# RPism_adapterboard_0V3.net
KiCad netlist of a schematic drawn in EAGLE
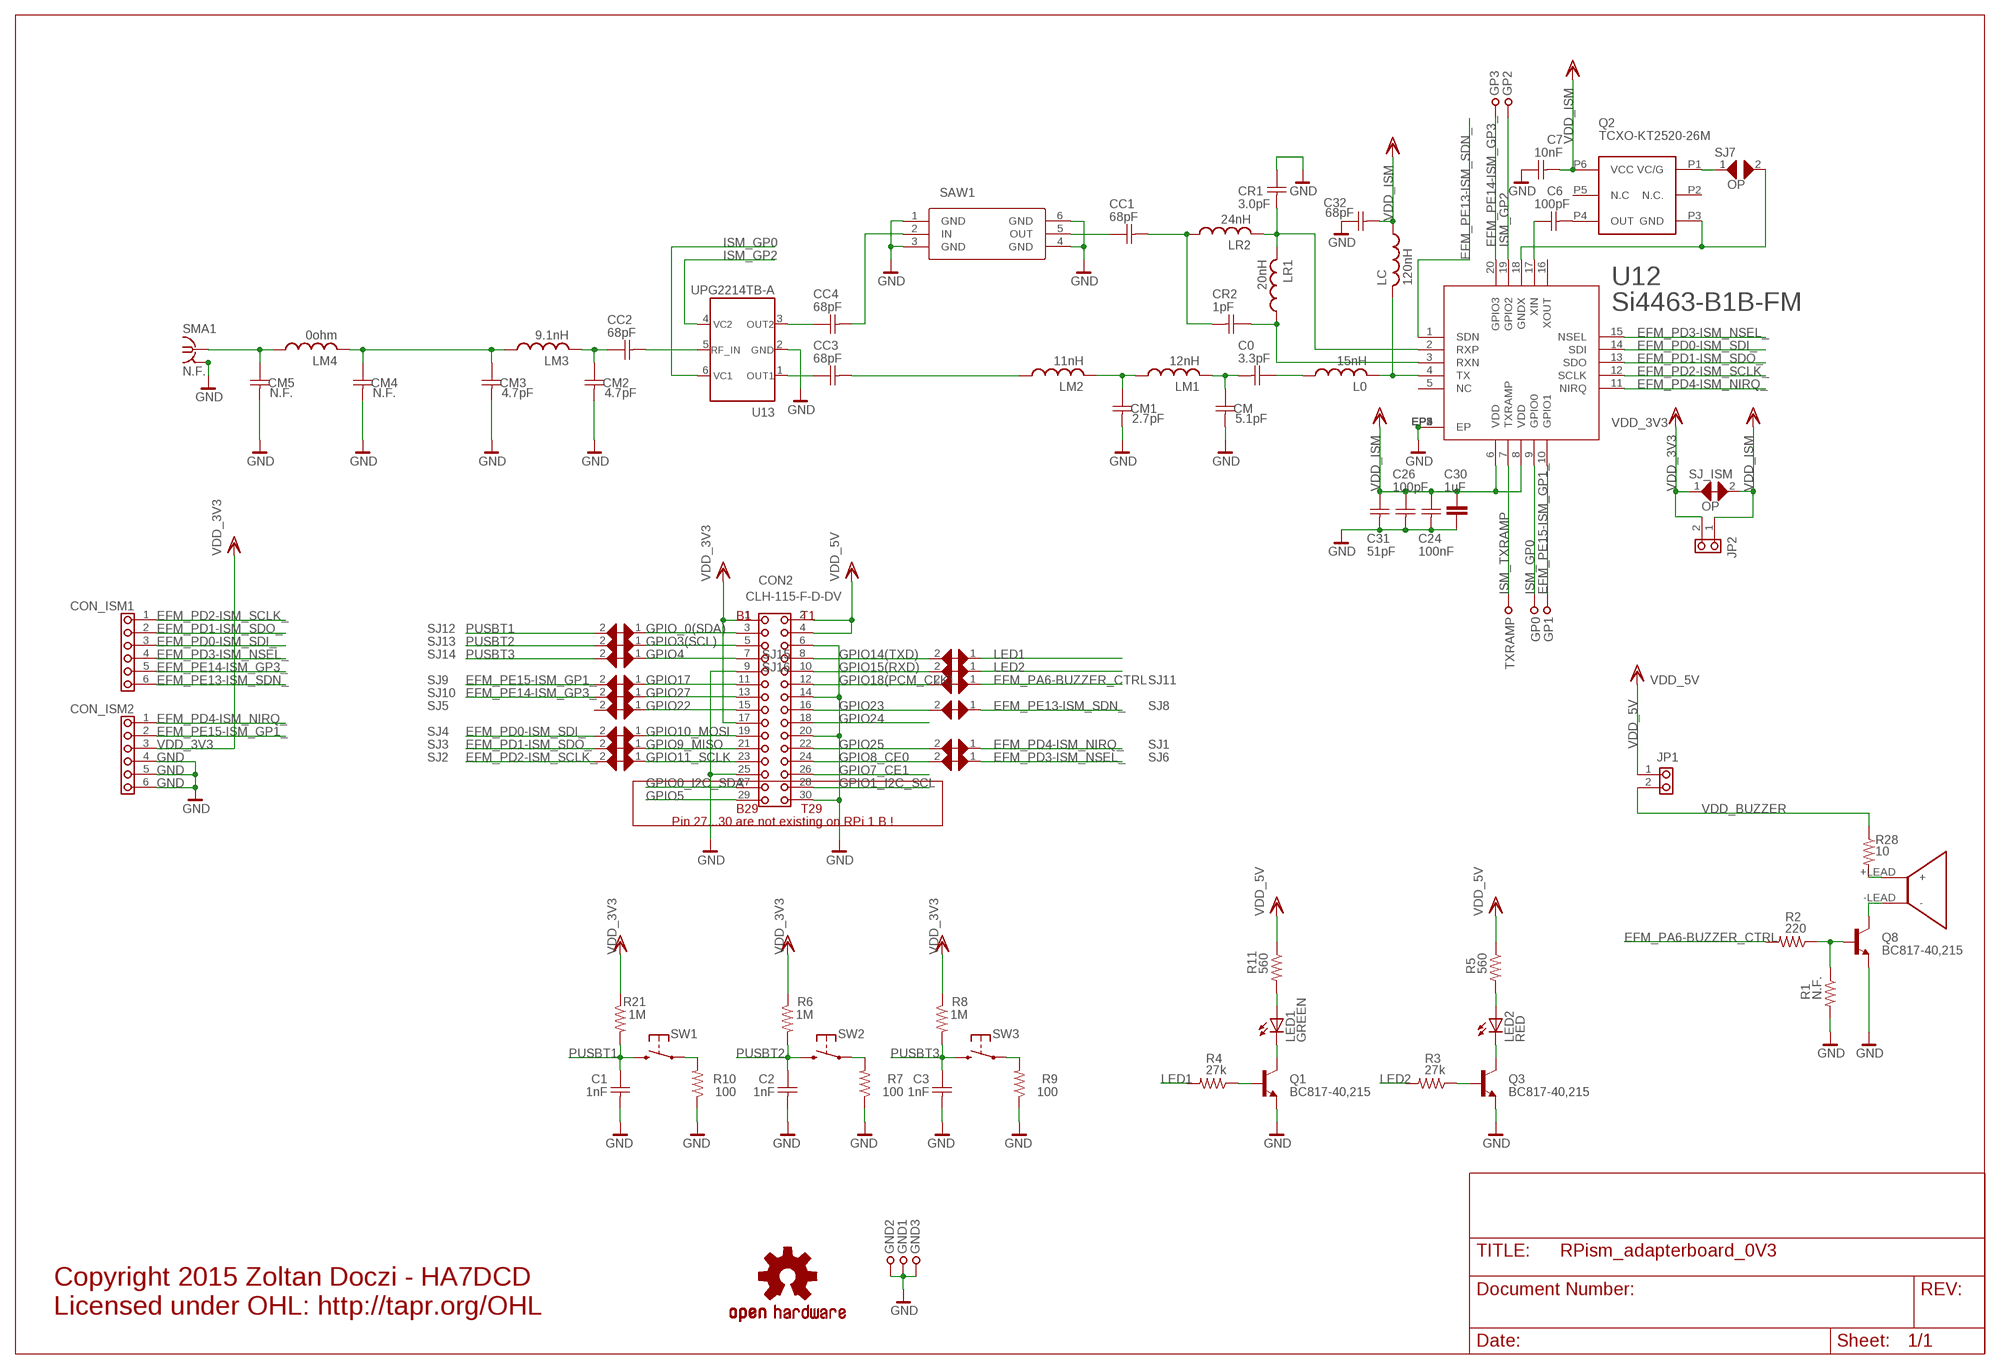
[diagram p0: schematic, sheet 1]

(export (version "E")
  (design (tool "Eeschema 10.0.6"))
  (components
    (comp (ref "BUZZ1")
      (value "SMT-0540-S-R")
      (footprint "eagle-import:SMT-0540-S-R")
      (libsource (lib "eagle-import") (part "SMT-0540-S-R"))
    )
    (comp (ref "C0")
      (value "3.3pF")
      (footprint "eagle-import:CAPC1005X60N")
      (libsource (lib "eagle-import") (part "CAP_GRM15"))
    )
    (comp (ref "C1")
      (value "1nF")
      (footprint "eagle-import:CAPC1005X60N")
      (libsource (lib "eagle-import") (part "CAP_GRM15"))
    )
    (comp (ref "C2")
      (value "1nF")
      (footprint "eagle-import:CAPC1005X60N")
      (libsource (lib "eagle-import") (part "CAP_GRM15"))
    )
    (comp (ref "C3")
      (value "1nF")
      (footprint "eagle-import:CAPC1005X60N")
      (libsource (lib "eagle-import") (part "CAP_GRM15"))
    )
    (comp (ref "C6")
      (value "100pF")
      (footprint "eagle-import:CAPC1005X60N")
      (libsource (lib "eagle-import") (part "CAP_GRM15"))
    )
    (comp (ref "C7")
      (value "10nF")
      (footprint "eagle-import:CAPC1005X60N")
      (libsource (lib "eagle-import") (part "CAP_GRM15"))
    )
    (comp (ref "C24")
      (value "100nF")
      (footprint "eagle-import:CAPC1005X60N")
      (libsource (lib "eagle-import") (part "CAP_GRM15"))
    )
    (comp (ref "C26")
      (value "100pF")
      (footprint "eagle-import:CAPC1005X60N")
      (libsource (lib "eagle-import") (part "CAP_GRM15"))
    )
    (comp (ref "C30")
      (value "1uF")
      (footprint "eagle-import:0603")
      (libsource (lib "eagle-import") (part "CAP-SMD0603"))
    )
    (comp (ref "C31")
      (value "51pF")
      (footprint "eagle-import:CAPC1005X60N")
      (libsource (lib "eagle-import") (part "CAP_GRM15"))
    )
    (comp (ref "C32")
      (value "68pF")
      (footprint "eagle-import:CAPC1005X60N")
      (libsource (lib "eagle-import") (part "CAP_GRM15"))
    )
    (comp (ref "CC1")
      (value "68pF")
      (footprint "eagle-import:CAPC1005X60N")
      (libsource (lib "eagle-import") (part "CAP_GRM15"))
    )
    (comp (ref "CC2")
      (value "68pF")
      (footprint "eagle-import:CAPC1005X60N")
      (libsource (lib "eagle-import") (part "CAP_GRM15"))
    )
    (comp (ref "CC3")
      (value "68pF")
      (footprint "eagle-import:CAPC1005X60N")
      (libsource (lib "eagle-import") (part "CAP_GRM15"))
    )
    (comp (ref "CC4")
      (value "68pF")
      (footprint "eagle-import:CAPC1005X60N")
      (libsource (lib "eagle-import") (part "CAP_GRM15"))
    )
    (comp (ref "CM")
      (value "5.1pF")
      (footprint "eagle-import:CAPC1005X60N")
      (libsource (lib "eagle-import") (part "CAP_GRM15"))
    )
    (comp (ref "CM1")
      (value "2.7pF")
      (footprint "eagle-import:CAPC1005X60N")
      (libsource (lib "eagle-import") (part "CAP_GRM15"))
    )
    (comp (ref "CM2")
      (value "4.7pF")
      (footprint "eagle-import:CAPC1005X60N")
      (libsource (lib "eagle-import") (part "CAP_GRM15"))
    )
    (comp (ref "CM3")
      (value "4.7pF")
      (footprint "eagle-import:CAPC1005X60N")
      (libsource (lib "eagle-import") (part "CAP_GRM15"))
    )
    (comp (ref "CM4")
      (value "N.F.")
      (footprint "eagle-import:CAPC1005X60N")
      (libsource (lib "eagle-import") (part "CAP_GRM15"))
    )
    (comp (ref "CM5")
      (value "N.F.")
      (footprint "eagle-import:CAPC1005X60N")
      (libsource (lib "eagle-import") (part "CAP_GRM15"))
    )
    (comp (ref "CON2")
      (value "CLH-115-F-D-DV")
      (footprint "eagle-import:2X15_SMT_CROSSPCB_ASSYM")
      (libsource (lib "eagle-import") (part "PINHD-2X15_SMD2X15"))
    )
    (comp (ref "CON_ISM1")
      (value "MALE__PIN6S-2MM")
      (footprint "eagle-import:PIN6S_2MM")
      (libsource (lib "eagle-import") (part "PIN6S-2MM"))
    )
    (comp (ref "CON_ISM2")
      (value "FEMALE__PIN6S-2MM")
      (footprint "eagle-import:PIN6S_2MM")
      (libsource (lib "eagle-import") (part "PIN6S-2MM"))
    )
    (comp (ref "CR1")
      (value "3.0pF")
      (footprint "eagle-import:CAPC1005X60N")
      (libsource (lib "eagle-import") (part "CAP_GRM15"))
    )
    (comp (ref "CR2")
      (value "1pF")
      (footprint "eagle-import:CAPC1005X60N")
      (libsource (lib "eagle-import") (part "CAP_GRM15"))
    )
    (comp (ref "GND1")
      (value "TESTPOINT39MIL")
      (footprint "eagle-import:TESTPOINT1,0")
      (libsource (lib "eagle-import") (part "lve_modositott_TESTPOINT39MIL"))
    )
    (comp (ref "GND2")
      (value "TESTPOINT39MIL")
      (footprint "eagle-import:TESTPOINT1,0")
      (libsource (lib "eagle-import") (part "lve_modositott_TESTPOINT39MIL"))
    )
    (comp (ref "GND3")
      (value "TESTPOINT39MIL")
      (footprint "eagle-import:TESTPOINT1,0")
      (libsource (lib "eagle-import") (part "lve_modositott_TESTPOINT39MIL"))
    )
    (comp (ref "GP0")
      (value "TESTPOINT20MIL")
      (footprint "eagle-import:TESTPOINT0,5")
      (libsource (lib "eagle-import") (part "TESTPOINT20MIL"))
    )
    (comp (ref "GP1")
      (value "TESTPOINT20MIL")
      (footprint "eagle-import:TESTPOINT0,5")
      (libsource (lib "eagle-import") (part "TESTPOINT20MIL"))
    )
    (comp (ref "GP2")
      (value "TESTPOINT20MIL")
      (footprint "eagle-import:TESTPOINT0,5")
      (libsource (lib "eagle-import") (part "TESTPOINT20MIL"))
    )
    (comp (ref "GP3")
      (value "TESTPOINT20MIL")
      (footprint "eagle-import:TESTPOINT0,5")
      (libsource (lib "eagle-import") (part "TESTPOINT20MIL"))
    )
    (comp (ref "JP1")
      (value "JUMPER2")
      (footprint "eagle-import:PIN2-1R")
      (libsource (lib "eagle-import") (part "JUMPER2"))
    )
    (comp (ref "JP2")
      (value "N.F.")
      (footprint "eagle-import:PIN2-1R")
      (libsource (lib "eagle-import") (part "JUMPER2"))
    )
    (comp (ref "L0")
      (value "15nH")
      (footprint "eagle-import:0402-INDUCT")
      (fields (field (name "PARTNR") "LQW15AN15NJ00") (field (name "VENDOR") "Murata"))
      (libsource (lib "eagle-import") (part "INDUCT_SMD"))
    )
    (comp (ref "LC")
      (value "120nH")
      (footprint "eagle-import:0402-INDUCT")
      (fields (field (name "PARTNR") "LQW15ANR12J00") (field (name "VENDOR") "Murata"))
      (libsource (lib "eagle-import") (part "INDUCT_SMD"))
    )
    (comp (ref "LED1")
      (value "GREEN")
      (footprint "eagle-import:LED-0603")
      (libsource (lib "eagle-import") (part "LED0603"))
    )
    (comp (ref "LED2")
      (value "RED")
      (footprint "eagle-import:LED-0603")
      (libsource (lib "eagle-import") (part "LED0603"))
    )
    (comp (ref "LM1")
      (value "12nH")
      (footprint "eagle-import:0402-INDUCT")
      (fields (field (name "PARTNR") "LQW15AN12NJ00") (field (name "VENDOR") "Murata"))
      (libsource (lib "eagle-import") (part "INDUCT_SMD"))
    )
    (comp (ref "LM2")
      (value "11nH")
      (footprint "eagle-import:0402-INDUCT")
      (fields (field (name "PARTNR") "LQW15AN11NJ00") (field (name "VENDOR") "Murata"))
      (libsource (lib "eagle-import") (part "INDUCT_SMD"))
    )
    (comp (ref "LM3")
      (value "9.1nH")
      (footprint "eagle-import:0402-INDUCT")
      (fields (field (name "PARTNR") "LQW15AN9N1J00") (field (name "VENDOR") "Murata"))
      (libsource (lib "eagle-import") (part "INDUCT_SMD"))
    )
    (comp (ref "LM4")
      (value "0ohm")
      (footprint "eagle-import:0402-INDUCT")
      (fields (field (name "PARTNR") "LQW15AN12NJ00") (field (name "VENDOR") "Murata"))
      (libsource (lib "eagle-import") (part "INDUCT_SMD"))
    )
    (comp (ref "LR1")
      (value "20nH")
      (footprint "eagle-import:0402-INDUCT")
      (fields (field (name "PARTNR") "LQW15AN20NJ00D") (field (name "VENDOR") "Murata"))
      (libsource (lib "eagle-import") (part "INDUCT_SMD"))
    )
    (comp (ref "LR2")
      (value "24nH")
      (footprint "eagle-import:0402-INDUCT")
      (fields (field (name "PARTNR") "LQW15AN24NJ00D") (field (name "VENDOR") "Murata"))
      (libsource (lib "eagle-import") (part "INDUCT_SMD"))
    )
    (comp (ref "Q1")
      (value "BC817-40,215")
      (footprint "eagle-import:SOT23-BEC")
      (libsource (lib "eagle-import") (part "BC817SMD-16LT1"))
    )
    (comp (ref "Q2")
      (value "TCXO-KT2520-26M")
      (footprint "eagle-import:TCXO_2.5X2MM")
      (libsource (lib "eagle-import") (part "TCXO-KT2520-26M"))
    )
    (comp (ref "Q3")
      (value "BC817-40,215")
      (footprint "eagle-import:SOT23-BEC")
      (libsource (lib "eagle-import") (part "BC817SMD-16LT1"))
    )
    (comp (ref "Q8")
      (value "BC817-40,215")
      (footprint "eagle-import:SOT23-BEC")
      (libsource (lib "eagle-import") (part "BC817SMD-16LT1"))
    )
    (comp (ref "R1")
      (value "N.F.")
      (footprint "eagle-import:R0402")
      (libsource (lib "eagle-import") (part "R-US_R0402"))
    )
    (comp (ref "R2")
      (value "220")
      (footprint "eagle-import:R0402")
      (libsource (lib "eagle-import") (part "R-US_R0402"))
    )
    (comp (ref "R3")
      (value "27k")
      (footprint "eagle-import:R0402")
      (libsource (lib "eagle-import") (part "R-US_R0402"))
    )
    (comp (ref "R4")
      (value "27k")
      (footprint "eagle-import:R0402")
      (libsource (lib "eagle-import") (part "R-US_R0402"))
    )
    (comp (ref "R5")
      (value "560")
      (footprint "eagle-import:R0402")
      (libsource (lib "eagle-import") (part "R-US_R0402"))
    )
    (comp (ref "R6")
      (value "1M")
      (footprint "eagle-import:R0402")
      (libsource (lib "eagle-import") (part "R-US_R0402"))
    )
    (comp (ref "R7")
      (value "100")
      (footprint "eagle-import:R0402")
      (libsource (lib "eagle-import") (part "R-US_R0402"))
    )
    (comp (ref "R8")
      (value "1M")
      (footprint "eagle-import:R0402")
      (libsource (lib "eagle-import") (part "R-US_R0402"))
    )
    (comp (ref "R9")
      (value "100")
      (footprint "eagle-import:R0402")
      (libsource (lib "eagle-import") (part "R-US_R0402"))
    )
    (comp (ref "R10")
      (value "100")
      (footprint "eagle-import:R0402")
      (libsource (lib "eagle-import") (part "R-US_R0402"))
    )
    (comp (ref "R11")
      (value "560")
      (footprint "eagle-import:R0402")
      (libsource (lib "eagle-import") (part "R-US_R0402"))
    )
    (comp (ref "R21")
      (value "1M")
      (footprint "eagle-import:R0402")
      (libsource (lib "eagle-import") (part "R-US_R0402"))
    )
    (comp (ref "R28")
      (value "10")
      (footprint "eagle-import:R0402")
      (libsource (lib "eagle-import") (part "R-US_R0402"))
    )
    (comp (ref "SAW1")
      (value "SAW_EPCOS_B3725")
      (footprint "eagle-import:DCC6C")
      (libsource (lib "eagle-import") (part "SAW_EPCOS_B3725"))
    )
    (comp (ref "SJ1")
      (value "JUMPER_SMD_MICRO_SHORT")
      (footprint "eagle-import:JUMPER_SMD_MICRO_SHORT")
      (libsource (lib "eagle-import") (part "JUMPER_SMD_MICRO_SHORT"))
    )
    (comp (ref "SJ2")
      (value "JUMPER_SMD_MICRO_SHORT")
      (footprint "eagle-import:JUMPER_SMD_MICRO_SHORT")
      (libsource (lib "eagle-import") (part "JUMPER_SMD_MICRO_SHORT"))
    )
    (comp (ref "SJ3")
      (value "JUMPER_SMD_MICRO_SHORT")
      (footprint "eagle-import:JUMPER_SMD_MICRO_SHORT")
      (libsource (lib "eagle-import") (part "JUMPER_SMD_MICRO_SHORT"))
    )
    (comp (ref "SJ4")
      (value "JUMPER_SMD_MICRO_SHORT")
      (footprint "eagle-import:JUMPER_SMD_MICRO_SHORT")
      (libsource (lib "eagle-import") (part "JUMPER_SMD_MICRO_SHORT"))
    )
    (comp (ref "SJ5")
      (value "JUMPER_SMD_MICRO_SHORT")
      (footprint "eagle-import:JUMPER_SMD_MICRO_SHORT")
      (libsource (lib "eagle-import") (part "JUMPER_SMD_MICRO_SHORT"))
    )
    (comp (ref "SJ6")
      (value "JUMPER_SMD_MICRO_SHORT")
      (footprint "eagle-import:JUMPER_SMD_MICRO_SHORT")
      (libsource (lib "eagle-import") (part "JUMPER_SMD_MICRO_SHORT"))
    )
    (comp (ref "SJ7")
      (value "OP")
      (footprint "eagle-import:JUMPER_SMD_MICRO")
      (libsource (lib "eagle-import") (part "JUMPER_SMD_MICROOPEN"))
    )
    (comp (ref "SJ8")
      (value "JUMPER_SMD_MICRO_SHORT")
      (footprint "eagle-import:JUMPER_SMD_MICRO_SHORT")
      (libsource (lib "eagle-import") (part "JUMPER_SMD_MICRO_SHORT"))
    )
    (comp (ref "SJ9")
      (value "JUMPER_SMD_MICRO_SHORT")
      (footprint "eagle-import:JUMPER_SMD_MICRO_SHORT")
      (libsource (lib "eagle-import") (part "JUMPER_SMD_MICRO_SHORT"))
    )
    (comp (ref "SJ10")
      (value "JUMPER_SMD_MICRO_SHORT")
      (footprint "eagle-import:JUMPER_SMD_MICRO_SHORT")
      (libsource (lib "eagle-import") (part "JUMPER_SMD_MICRO_SHORT"))
    )
    (comp (ref "SJ11")
      (value "JUMPER_SMD_MICRO_SHORT")
      (footprint "eagle-import:JUMPER_SMD_MICRO_SHORT")
      (libsource (lib "eagle-import") (part "JUMPER_SMD_MICRO_SHORT"))
    )
    (comp (ref "SJ12")
      (value "JUMPER_SMD_MICRO_SHORT")
      (footprint "eagle-import:JUMPER_SMD_MICRO_SHORT")
      (libsource (lib "eagle-import") (part "JUMPER_SMD_MICRO_SHORT"))
    )
    (comp (ref "SJ13")
      (value "JUMPER_SMD_MICRO_SHORT")
      (footprint "eagle-import:JUMPER_SMD_MICRO_SHORT")
      (libsource (lib "eagle-import") (part "JUMPER_SMD_MICRO_SHORT"))
    )
    (comp (ref "SJ14")
      (value "JUMPER_SMD_MICRO_SHORT")
      (footprint "eagle-import:JUMPER_SMD_MICRO_SHORT")
      (libsource (lib "eagle-import") (part "JUMPER_SMD_MICRO_SHORT"))
    )
    (comp (ref "SJ15")
      (value "JUMPER_SMD_MICRO_SHORT")
      (footprint "eagle-import:JUMPER_SMD_MICRO_SHORT")
      (libsource (lib "eagle-import") (part "JUMPER_SMD_MICRO_SHORT"))
    )
    (comp (ref "SJ16")
      (value "JUMPER_SMD_MICRO_SHORT")
      (footprint "eagle-import:JUMPER_SMD_MICRO_SHORT")
      (libsource (lib "eagle-import") (part "JUMPER_SMD_MICRO_SHORT"))
    )
    (comp (ref "SJ_ISM")
      (value "OP")
      (footprint "eagle-import:JUMPER_SMD_MICRO_SHORT")
      (libsource (lib "eagle-import") (part "JUMPER_SMD_MICRO_SHORT"))
    )
    (comp (ref "SMA1")
      (value "N.F.")
      (footprint "eagle-import:BU-SMA-V")
      (libsource (lib "eagle-import") (part "SMAVERTICAL"))
    )
    (comp (ref "SW1")
      (value "DTSM_32N")
      (footprint "eagle-import:DTSM_32N")
      (libsource (lib "eagle-import") (part "PUSHBUTTON1"))
    )
    (comp (ref "SW2")
      (value "DTSM_32N")
      (footprint "eagle-import:DTSM_32N")
      (libsource (lib "eagle-import") (part "PUSHBUTTON1"))
    )
    (comp (ref "SW3")
      (value "DTSM_32N")
      (footprint "eagle-import:DTSM_32N")
      (libsource (lib "eagle-import") (part "PUSHBUTTON1"))
    )
    (comp (ref "TXRAMP")
      (value "TESTPOINT20MIL")
      (footprint "eagle-import:TESTPOINT0,5")
      (libsource (lib "eagle-import") (part "TESTPOINT20MIL"))
    )
    (comp (ref "U$15")
      (value "OSHW-LOGOL")
      (footprint "eagle-import:OSHW-LOGO-L")
      (libsource (lib "eagle-import") (part "OSHW-LOGOL"))
    )
    (comp (ref "U12")
      (value "Si4463-B1B-FM")
      (footprint "eagle-import:QFN-20_PRO2_VERIFIED")
      (libsource (lib "eagle-import") (part "SI4463"))
    )
    (comp (ref "U13")
      (value "UPG2214TB-A")
      (footprint "eagle-import:6-PIN_SUPER_MINIMOLD")
      (libsource (lib "eagle-import") (part "UPG2214TB6SM"))
    )
  )
  (nets
    (net (code "1") (name "/EFM_PA6-BUZZER_CTRL") (class "Default")
      (node (ref "R2") (pin "2") (pinfunction "2_2") (pintype "passive"))
      (node (ref "SJ11") (pin "1") (pinfunction "1_1") (pintype "passive"))
    )
    (net (code "2") (name "/EFM_PD0-ISM_SDI_") (class "Default")
      (node (ref "CON_ISM1") (pin "3") (pinfunction "3_3") (pintype "passive"))
      (node (ref "SJ4") (pin "2") (pinfunction "2_2") (pintype "passive"))
      (node (ref "U12") (pin "14") (pinfunction "SDI_14") (pintype "input"))
    )
    (net (code "3") (name "/EFM_PD1-ISM_SDO_") (class "Default")
      (node (ref "CON_ISM1") (pin "2") (pinfunction "2_2") (pintype "passive"))
      (node (ref "SJ3") (pin "2") (pinfunction "2_2") (pintype "passive"))
      (node (ref "U12") (pin "13") (pinfunction "SDO_13") (pintype "output"))
    )
    (net (code "4") (name "/EFM_PD2-ISM_SCLK_") (class "Default")
      (node (ref "CON_ISM1") (pin "1") (pinfunction "1_1") (pintype "passive"))
      (node (ref "SJ2") (pin "2") (pinfunction "2_2") (pintype "passive"))
      (node (ref "U12") (pin "12") (pinfunction "SCLK_12") (pintype "input"))
    )
    (net (code "5") (name "/EFM_PD3-ISM_NSEL_") (class "Default")
      (node (ref "CON_ISM1") (pin "4") (pinfunction "4_4") (pintype "passive"))
      (node (ref "SJ6") (pin "1") (pinfunction "1_1") (pintype "passive"))
      (node (ref "U12") (pin "15") (pinfunction "NSEL_15") (pintype "input"))
    )
    (net (code "6") (name "/EFM_PD4-ISM_NIRQ_") (class "Default")
      (node (ref "CON_ISM2") (pin "1") (pinfunction "1_1") (pintype "passive"))
      (node (ref "SJ1") (pin "1") (pinfunction "1_1") (pintype "passive"))
      (node (ref "U12") (pin "11") (pinfunction "NIRQ_11") (pintype "output"))
    )
    (net (code "7") (name "/EFM_PE13-ISM_SDN_") (class "Default")
      (node (ref "CON_ISM1") (pin "6") (pinfunction "6_6") (pintype "passive"))
      (node (ref "SJ8") (pin "1") (pinfunction "1_1") (pintype "passive"))
      (node (ref "U12") (pin "1") (pinfunction "SDN_1") (pintype "input"))
    )
    (net (code "8") (name "/EFM_PE14-ISM_GP3_") (class "Default")
      (node (ref "CON_ISM1") (pin "5") (pinfunction "5_5") (pintype "passive"))
      (node (ref "GP3") (pin "1") (pinfunction "P$1_1") (pintype "passive"))
      (node (ref "SJ10") (pin "2") (pinfunction "2_2") (pintype "passive"))
      (node (ref "U12") (pin "20") (pinfunction "GPIO3_20") (pintype "bidirectional"))
    )
    (net (code "9") (name "/EFM_PE15-ISM_GP1_") (class "Default")
      (node (ref "CON_ISM2") (pin "2") (pinfunction "2_2") (pintype "passive"))
      (node (ref "GP1") (pin "1") (pinfunction "P$1_1") (pintype "passive"))
      (node (ref "SJ9") (pin "2") (pinfunction "2_2") (pintype "passive"))
      (node (ref "U12") (pin "10") (pinfunction "GPIO1_10") (pintype "bidirectional"))
    )
    (net (code "10") (name "/GPIO0_I2C_SDA") (class "Default")
      (node (ref "CON2") (pin "27") (pinfunction "27_27") (pintype "passive"))
    )
    (net (code "11") (name "/GPIO1_I2C_SCL") (class "Default")
      (node (ref "CON2") (pin "28") (pinfunction "28_28") (pintype "passive"))
    )
    (net (code "12") (name "/GPIO3(SCL)") (class "Default")
      (node (ref "CON2") (pin "5") (pinfunction "5_5") (pintype "passive"))
      (node (ref "SJ13") (pin "1") (pinfunction "1_1") (pintype "passive"))
    )
    (net (code "13") (name "/GPIO4") (class "Default")
      (node (ref "CON2") (pin "7") (pinfunction "7_7") (pintype "passive"))
      (node (ref "SJ14") (pin "1") (pinfunction "1_1") (pintype "passive"))
    )
    (net (code "14") (name "/GPIO5") (class "Default")
      (node (ref "CON2") (pin "29") (pinfunction "29_29") (pintype "passive"))
    )
    (net (code "15") (name "/GPIO7_CE1") (class "Default")
      (node (ref "CON2") (pin "26") (pinfunction "26_26") (pintype "passive"))
    )
    (net (code "16") (name "/GPIO8_CE0") (class "Default")
      (node (ref "CON2") (pin "24") (pinfunction "24_24") (pintype "passive"))
      (node (ref "SJ6") (pin "2") (pinfunction "2_2") (pintype "passive"))
    )
    (net (code "17") (name "/GPIO9_MISO") (class "Default")
      (node (ref "CON2") (pin "21") (pinfunction "21_21") (pintype "passive"))
      (node (ref "SJ3") (pin "1") (pinfunction "1_1") (pintype "passive"))
    )
    (net (code "18") (name "/GPIO10_MOSI") (class "Default")
      (node (ref "CON2") (pin "19") (pinfunction "19_19") (pintype "passive"))
      (node (ref "SJ4") (pin "1") (pinfunction "1_1") (pintype "passive"))
    )
    (net (code "19") (name "/GPIO11_SCLK") (class "Default")
      (node (ref "CON2") (pin "23") (pinfunction "23_23") (pintype "passive"))
      (node (ref "SJ2") (pin "1") (pinfunction "1_1") (pintype "passive"))
    )
    (net (code "20") (name "/GPIO14(TXD)") (class "Default")
      (node (ref "CON2") (pin "8") (pinfunction "8_8") (pintype "passive"))
      (node (ref "SJ15") (pin "2") (pinfunction "2_2") (pintype "passive"))
    )
    (net (code "21") (name "/GPIO15(RXD)") (class "Default")
      (node (ref "CON2") (pin "10") (pinfunction "10_10") (pintype "passive"))
      (node (ref "SJ16") (pin "2") (pinfunction "2_2") (pintype "passive"))
    )
    (net (code "22") (name "/GPIO17") (class "Default")
      (node (ref "CON2") (pin "11") (pinfunction "11_11") (pintype "passive"))
      (node (ref "SJ9") (pin "1") (pinfunction "1_1") (pintype "passive"))
    )
    (net (code "23") (name "/GPIO18(PCM_CLK)") (class "Default")
      (node (ref "CON2") (pin "12") (pinfunction "12_12") (pintype "passive"))
      (node (ref "SJ11") (pin "2") (pinfunction "2_2") (pintype "passive"))
    )
    (net (code "24") (name "/GPIO22") (class "Default")
      (node (ref "CON2") (pin "15") (pinfunction "15_15") (pintype "passive"))
      (node (ref "SJ5") (pin "1") (pinfunction "1_1") (pintype "passive"))
    )
    (net (code "25") (name "/GPIO23") (class "Default")
      (node (ref "CON2") (pin "16") (pinfunction "16_16") (pintype "passive"))
      (node (ref "SJ8") (pin "2") (pinfunction "2_2") (pintype "passive"))
    )
    (net (code "26") (name "/GPIO24") (class "Default")
      (node (ref "CON2") (pin "18") (pinfunction "18_18") (pintype "passive"))
    )
    (net (code "27") (name "/GPIO25") (class "Default")
      (node (ref "CON2") (pin "22") (pinfunction "22_22") (pintype "passive"))
      (node (ref "SJ1") (pin "2") (pinfunction "2_2") (pintype "passive"))
    )
    (net (code "28") (name "/GPIO27") (class "Default")
      (node (ref "CON2") (pin "13") (pinfunction "13_13") (pintype "passive"))
      (node (ref "SJ10") (pin "1") (pinfunction "1_1") (pintype "passive"))
    )
    (net (code "29") (name "/GPIO_0(SDA)") (class "Default")
      (node (ref "CON2") (pin "3") (pinfunction "3_3") (pintype "passive"))
      (node (ref "SJ12") (pin "1") (pinfunction "1_1") (pintype "passive"))
    )
    (net (code "30") (name "/ISM_GP0") (class "Default")
      (node (ref "GP0") (pin "1") (pinfunction "P$1_1") (pintype "passive"))
      (node (ref "U12") (pin "9") (pinfunction "GPIO0_9") (pintype "bidirectional"))
      (node (ref "U13") (pin "6") (pinfunction "P$6_6") (pintype "input"))
    )
    (net (code "31") (name "/ISM_GP2") (class "Default")
      (node (ref "GP2") (pin "1") (pinfunction "P$1_1") (pintype "passive"))
      (node (ref "U12") (pin "19") (pinfunction "GPIO2_19") (pintype "bidirectional"))
      (node (ref "U13") (pin "4") (pinfunction "P$4_4") (pintype "input"))
    )
    (net (code "32") (name "/ISM_TXRAMP") (class "Default")
      (node (ref "TXRAMP") (pin "1") (pinfunction "P$1_1") (pintype "passive"))
      (node (ref "U12") (pin "7") (pinfunction "TXRAMP_7") (pintype "output"))
    )
    (net (code "33") (name "/LED1") (class "Default")
      (node (ref "R4") (pin "2") (pinfunction "2_2") (pintype "passive"))
      (node (ref "SJ15") (pin "1") (pinfunction "1_1") (pintype "passive"))
    )
    (net (code "34") (name "/LED2") (class "Default")
      (node (ref "R3") (pin "2") (pinfunction "2_2") (pintype "passive"))
      (node (ref "SJ16") (pin "1") (pinfunction "1_1") (pintype "passive"))
    )
    (net (code "35") (name "/PUSBT1") (class "Default")
      (node (ref "C1") (pin "1") (pinfunction "C1_1") (pintype "passive"))
      (node (ref "R21") (pin "2") (pinfunction "2_2") (pintype "passive"))
      (node (ref "SJ12") (pin "2") (pinfunction "2_2") (pintype "passive"))
      (node (ref "SW1") (pin "2") (pinfunction "2_2") (pintype "passive"))
    )
    (net (code "36") (name "/PUSBT2") (class "Default")
      (node (ref "C2") (pin "1") (pinfunction "C1_1") (pintype "passive"))
      (node (ref "R6") (pin "2") (pinfunction "2_2") (pintype "passive"))
      (node (ref "SJ13") (pin "2") (pinfunction "2_2") (pintype "passive"))
      (node (ref "SW2") (pin "2") (pinfunction "2_2") (pintype "passive"))
    )
    (net (code "37") (name "/PUSBT3") (class "Default")
      (node (ref "C3") (pin "1") (pinfunction "C1_1") (pintype "passive"))
      (node (ref "R8") (pin "2") (pinfunction "2_2") (pintype "passive"))
      (node (ref "SJ14") (pin "2") (pinfunction "2_2") (pintype "passive"))
      (node (ref "SW3") (pin "2") (pinfunction "2_2") (pintype "passive"))
    )
    (net (code "38") (name "/VDD_BUZZER") (class "Default")
      (node (ref "JP1") (pin "2") (pinfunction "B_2") (pintype "passive"))
      (node (ref "R28") (pin "1") (pinfunction "1_1") (pintype "passive"))
    )
    (net (code "39") (name "GND") (class "Default")
      (node (ref "C1") (pin "2") (pinfunction "C2_2") (pintype "passive"))
      (node (ref "C2") (pin "2") (pinfunction "C2_2") (pintype "passive"))
      (node (ref "C24") (pin "2") (pinfunction "C2_2") (pintype "passive"))
      (node (ref "C26") (pin "2") (pinfunction "C2_2") (pintype "passive"))
      (node (ref "C3") (pin "2") (pinfunction "C2_2") (pintype "passive"))
      (node (ref "C30") (pin "1") (pinfunction "1_1") (pintype "passive"))
      (node (ref "C31") (pin "2") (pinfunction "C2_2") (pintype "passive"))
      (node (ref "C32") (pin "1") (pinfunction "C1_1") (pintype "passive"))
      (node (ref "C7") (pin "1") (pinfunction "C1_1") (pintype "passive"))
      (node (ref "CM") (pin "2") (pinfunction "C2_2") (pintype "passive"))
      (node (ref "CM1") (pin "2") (pinfunction "C2_2") (pintype "passive"))
      (node (ref "CM2") (pin "2") (pinfunction "C2_2") (pintype "passive"))
      (node (ref "CM3") (pin "2") (pinfunction "C2_2") (pintype "passive"))
      (node (ref "CM4") (pin "2") (pinfunction "C2_2") (pintype "passive"))
      (node (ref "CM5") (pin "2") (pinfunction "C2_2") (pintype "passive"))
      (node (ref "CON2") (pin "14") (pinfunction "14_14") (pintype "passive"))
      (node (ref "CON2") (pin "20") (pinfunction "20_20") (pintype "passive"))
      (node (ref "CON2") (pin "25") (pinfunction "25_25") (pintype "passive"))
      (node (ref "CON2") (pin "30") (pinfunction "30_30") (pintype "passive"))
      (node (ref "CON2") (pin "6") (pinfunction "6_6") (pintype "passive"))
      (node (ref "CON2") (pin "9") (pinfunction "9_9") (pintype "passive"))
      (node (ref "CON_ISM2") (pin "4") (pinfunction "4_4") (pintype "passive"))
      (node (ref "CON_ISM2") (pin "5") (pinfunction "5_5") (pintype "passive"))
      (node (ref "CON_ISM2") (pin "6") (pinfunction "6_6") (pintype "passive"))
      (node (ref "CR1") (pin "1") (pinfunction "C1_1") (pintype "passive"))
      (node (ref "GND1") (pin "1") (pinfunction "P$1_1") (pintype "passive"))
      (node (ref "GND2") (pin "1") (pinfunction "P$1_1") (pintype "passive"))
      (node (ref "GND3") (pin "1") (pinfunction "P$1_1") (pintype "passive"))
      (node (ref "Q1") (pin "E") (pinfunction "E_E") (pintype "passive"))
      (node (ref "Q3") (pin "E") (pinfunction "E_E") (pintype "passive"))
      (node (ref "Q8") (pin "E") (pinfunction "E_E") (pintype "passive"))
      (node (ref "R1") (pin "2") (pinfunction "2_2") (pintype "passive"))
      (node (ref "R10") (pin "1") (pinfunction "1_1") (pintype "passive"))
      (node (ref "R7") (pin "1") (pinfunction "1_1") (pintype "passive"))
      (node (ref "R9") (pin "1") (pinfunction "1_1") (pintype "passive"))
      (node (ref "SAW1") (pin "1") (pinfunction "GND_1") (pintype "bidirectional"))
      (node (ref "SAW1") (pin "3") (pinfunction "GND_3") (pintype "bidirectional"))
      (node (ref "SAW1") (pin "4") (pinfunction "GND_4") (pintype "bidirectional"))
      (node (ref "SAW1") (pin "6") (pinfunction "GND_6") (pintype "bidirectional"))
      (node (ref "SMA1") (pin "2") (pinfunction "2_2") (pintype "passive"))
      (node (ref "SMA1") (pin "3") (pinfunction "3_3") (pintype "passive"))
      (node (ref "SMA1") (pin "4") (pinfunction "4_4") (pintype "passive"))
      (node (ref "SMA1") (pin "5") (pinfunction "5_5") (pintype "passive"))
      (node (ref "U12") (pin "EP0") (pinfunction "EP_EP0") (pintype "power_in"))
      (node (ref "U12") (pin "EP1") (pinfunction "EP_EP1") (pintype "power_in"))
      (node (ref "U12") (pin "EP2") (pinfunction "EP_EP2") (pintype "power_in"))
      (node (ref "U12") (pin "EP3") (pinfunction "EP_EP3") (pintype "power_in"))
      (node (ref "U12") (pin "EP4") (pinfunction "EP_EP4") (pintype "power_in"))
      (node (ref "U12") (pin "EP5") (pinfunction "EP_EP5") (pintype "power_in"))
      (node (ref "U13") (pin "2") (pinfunction "P$2_2") (pintype "power_in"))
    )
    (net (code "40") (name "Net-(BUZZ1-+)") (class "Default")
      (node (ref "BUZZ1") (pin "+LEAD") (pinfunction "+_+LEAD") (pintype "bidirectional"))
      (node (ref "R28") (pin "2") (pinfunction "2_2") (pintype "passive"))
    )
    (net (code "41") (name "Net-(BUZZ1--)") (class "Default")
      (node (ref "BUZZ1") (pin "-LEAD") (pinfunction "-_-LEAD") (pintype "bidirectional"))
      (node (ref "Q8") (pin "C") (pinfunction "C_C") (pintype "passive"))
    )
    (net (code "42") (name "Net-(C0-C1)") (class "Default")
      (node (ref "C0") (pin "1") (pinfunction "C1_1") (pintype "passive"))
      (node (ref "L0") (pin "1") (pinfunction "1_1") (pintype "passive"))
    )
    (net (code "43") (name "Net-(C0-C2)") (class "Default")
      (node (ref "C0") (pin "2") (pinfunction "C2_2") (pintype "passive"))
      (node (ref "CM") (pin "1") (pinfunction "C1_1") (pintype "passive"))
      (node (ref "LM1") (pin "2") (pinfunction "2_2") (pintype "passive"))
    )
    (net (code "44") (name "Net-(C6-C1)") (class "Default")
      (node (ref "C6") (pin "1") (pinfunction "C1_1") (pintype "passive"))
      (node (ref "U12") (pin "17") (pinfunction "XIN_17") (pintype "input"))
    )
    (net (code "45") (name "Net-(C6-C2)") (class "Default")
      (node (ref "C6") (pin "2") (pinfunction "C2_2") (pintype "passive"))
      (node (ref "Q2") (pin "P4") (pinfunction "OUT_P4") (pintype "output"))
    )
    (net (code "46") (name "Net-(CC1-C1)") (class "Default")
      (node (ref "CC1") (pin "1") (pinfunction "C1_1") (pintype "passive"))
      (node (ref "SAW1") (pin "5") (pinfunction "OUT_5") (pintype "bidirectional"))
    )
    (net (code "47") (name "Net-(CC1-C2)") (class "Default")
      (node (ref "CC1") (pin "2") (pinfunction "C2_2") (pintype "passive"))
      (node (ref "CR2") (pin "2") (pinfunction "C2_2") (pintype "passive"))
      (node (ref "LR2") (pin "1") (pinfunction "1_1") (pintype "passive"))
    )
    (net (code "48") (name "Net-(CC2-C1)") (class "Default")
      (node (ref "CC2") (pin "1") (pinfunction "C1_1") (pintype "passive"))
      (node (ref "CM2") (pin "1") (pinfunction "C1_1") (pintype "passive"))
      (node (ref "LM3") (pin "2") (pinfunction "2_2") (pintype "passive"))
    )
    (net (code "49") (name "Net-(CC2-C2)") (class "Default")
      (node (ref "CC2") (pin "2") (pinfunction "C2_2") (pintype "passive"))
      (node (ref "U13") (pin "5") (pinfunction "P$5_5") (pintype "input"))
    )
    (net (code "50") (name "Net-(CC3-C1)") (class "Default")
      (node (ref "CC3") (pin "1") (pinfunction "C1_1") (pintype "passive"))
      (node (ref "U13") (pin "1") (pinfunction "P$1_1") (pintype "output"))
    )
    (net (code "51") (name "Net-(CC3-C2)") (class "Default")
      (node (ref "CC3") (pin "2") (pinfunction "C2_2") (pintype "passive"))
      (node (ref "LM2") (pin "1") (pinfunction "1_1") (pintype "passive"))
    )
    (net (code "52") (name "Net-(CC4-C1)") (class "Default")
      (node (ref "CC4") (pin "1") (pinfunction "C1_1") (pintype "passive"))
      (node (ref "U13") (pin "3") (pinfunction "P$3_3") (pintype "output"))
    )
    (net (code "53") (name "Net-(CC4-C2)") (class "Default")
      (node (ref "CC4") (pin "2") (pinfunction "C2_2") (pintype "passive"))
      (node (ref "SAW1") (pin "2") (pinfunction "IN_2") (pintype "bidirectional"))
    )
    (net (code "54") (name "Net-(CM1-C1)") (class "Default")
      (node (ref "CM1") (pin "1") (pinfunction "C1_1") (pintype "passive"))
      (node (ref "LM1") (pin "1") (pinfunction "1_1") (pintype "passive"))
      (node (ref "LM2") (pin "2") (pinfunction "2_2") (pintype "passive"))
    )
    (net (code "55") (name "Net-(CM3-C1)") (class "Default")
      (node (ref "CM3") (pin "1") (pinfunction "C1_1") (pintype "passive"))
      (node (ref "CM4") (pin "1") (pinfunction "C1_1") (pintype "passive"))
      (node (ref "LM3") (pin "1") (pinfunction "1_1") (pintype "passive"))
      (node (ref "LM4") (pin "2") (pinfunction "2_2") (pintype "passive"))
    )
    (net (code "56") (name "Net-(CM5-C1)") (class "Default")
      (node (ref "CM5") (pin "1") (pinfunction "C1_1") (pintype "passive"))
      (node (ref "LM4") (pin "1") (pinfunction "1_1") (pintype "passive"))
      (node (ref "SMA1") (pin "1") (pinfunction "1_1") (pintype "passive"))
    )
    (net (code "57") (name "Net-(CR1-C2)") (class "Default")
      (node (ref "CR1") (pin "2") (pinfunction "C2_2") (pintype "passive"))
      (node (ref "LR1") (pin "2") (pinfunction "2_2") (pintype "passive"))
      (node (ref "LR2") (pin "2") (pinfunction "2_2") (pintype "passive"))
      (node (ref "U12") (pin "2") (pinfunction "RXP_2") (pintype "input"))
    )
    (net (code "58") (name "Net-(CR2-C1)") (class "Default")
      (node (ref "CR2") (pin "1") (pinfunction "C1_1") (pintype "passive"))
      (node (ref "LR1") (pin "1") (pinfunction "1_1") (pintype "passive"))
      (node (ref "U12") (pin "3") (pinfunction "RXN_3") (pintype "input"))
    )
    (net (code "59") (name "Net-(LED1-PadA)") (class "Default")
      (node (ref "LED1") (pin "A") (pinfunction "A_A") (pintype "passive"))
      (node (ref "R11") (pin "2") (pinfunction "2_2") (pintype "passive"))
    )
    (net (code "60") (name "Net-(LED1-PadC)") (class "Default")
      (node (ref "LED1") (pin "C") (pinfunction "C_C") (pintype "passive"))
      (node (ref "Q1") (pin "C") (pinfunction "C_C") (pintype "passive"))
    )
    (net (code "61") (name "Net-(LED2-PadA)") (class "Default")
      (node (ref "LED2") (pin "A") (pinfunction "A_A") (pintype "passive"))
      (node (ref "R5") (pin "2") (pinfunction "2_2") (pintype "passive"))
    )
    (net (code "62") (name "Net-(LED2-PadC)") (class "Default")
      (node (ref "LED2") (pin "C") (pinfunction "C_C") (pintype "passive"))
      (node (ref "Q3") (pin "C") (pinfunction "C_C") (pintype "passive"))
    )
    (net (code "63") (name "Net-(Q1-PadB)") (class "Default")
      (node (ref "Q1") (pin "B") (pinfunction "B_B") (pintype "passive"))
      (node (ref "R4") (pin "1") (pinfunction "1_1") (pintype "passive"))
    )
    (net (code "64") (name "Net-(Q2-GND)") (class "Default")
      (node (ref "Q2") (pin "P3") (pinfunction "GND_P3") (pintype "power_in"))
      (node (ref "SJ7") (pin "2") (pinfunction "2_2") (pintype "passive"))
      (node (ref "U12") (pin "18") (pinfunction "GNDX_18") (pintype "power_in"))
    )
    (net (code "65") (name "Net-(Q2-VC{slash}G)") (class "Default")
      (node (ref "Q2") (pin "P1") (pinfunction "VC/G_P1") (pintype "bidirectional"))
      (node (ref "SJ7") (pin "1") (pinfunction "1_1") (pintype "passive"))
    )
    (net (code "66") (name "Net-(Q3-PadB)") (class "Default")
      (node (ref "Q3") (pin "B") (pinfunction "B_B") (pintype "passive"))
      (node (ref "R3") (pin "1") (pinfunction "1_1") (pintype "passive"))
    )
    (net (code "67") (name "Net-(Q8-PadB)") (class "Default")
      (node (ref "Q8") (pin "B") (pinfunction "B_B") (pintype "passive"))
      (node (ref "R1") (pin "1") (pinfunction "1_1") (pintype "passive"))
      (node (ref "R2") (pin "1") (pinfunction "1_1") (pintype "passive"))
    )
    (net (code "68") (name "Net-(R7-Pad2)") (class "Default")
      (node (ref "R7") (pin "2") (pinfunction "2_2") (pintype "passive"))
      (node (ref "SW2") (pin "1") (pinfunction "1_1") (pintype "passive"))
    )
    (net (code "69") (name "Net-(R9-Pad2)") (class "Default")
      (node (ref "R9") (pin "2") (pinfunction "2_2") (pintype "passive"))
      (node (ref "SW3") (pin "1") (pinfunction "1_1") (pintype "passive"))
    )
    (net (code "70") (name "Net-(R10-Pad2)") (class "Default")
      (node (ref "R10") (pin "2") (pinfunction "2_2") (pintype "passive"))
      (node (ref "SW1") (pin "1") (pinfunction "1_1") (pintype "passive"))
    )
    (net (code "71") (name "Net-(U12-TX)") (class "Default")
      (node (ref "L0") (pin "2") (pinfunction "2_2") (pintype "passive"))
      (node (ref "LC") (pin "2") (pinfunction "2_2") (pintype "passive"))
      (node (ref "U12") (pin "4") (pinfunction "TX_4") (pintype "output"))
    )
    (net (code "72") (name "VDD_3V3") (class "Default")
      (node (ref "CON2") (pin "1") (pinfunction "1_1") (pintype "passive"))
      (node (ref "CON2") (pin "17") (pinfunction "17_17") (pintype "passive"))
      (node (ref "CON_ISM2") (pin "3") (pinfunction "3_3") (pintype "passive"))
      (node (ref "JP2") (pin "2") (pinfunction "B_2") (pintype "passive"))
      (node (ref "R21") (pin "1") (pinfunction "1_1") (pintype "passive"))
      (node (ref "R6") (pin "1") (pinfunction "1_1") (pintype "passive"))
      (node (ref "R8") (pin "1") (pinfunction "1_1") (pintype "passive"))
      (node (ref "SJ_ISM") (pin "1") (pinfunction "1_1") (pintype "passive"))
    )
    (net (code "73") (name "VDD_5V") (class "Default")
      (node (ref "CON2") (pin "2") (pinfunction "2_2") (pintype "passive"))
      (node (ref "CON2") (pin "4") (pinfunction "4_4") (pintype "passive"))
      (node (ref "JP1") (pin "1") (pinfunction "A_1") (pintype "passive"))
      (node (ref "R11") (pin "1") (pinfunction "1_1") (pintype "passive"))
      (node (ref "R5") (pin "1") (pinfunction "1_1") (pintype "passive"))
    )
    (net (code "74") (name "VDD_ISM") (class "Default")
      (node (ref "C24") (pin "1") (pinfunction "C1_1") (pintype "passive"))
      (node (ref "C26") (pin "1") (pinfunction "C1_1") (pintype "passive"))
      (node (ref "C30") (pin "2") (pinfunction "2_2") (pintype "passive"))
      (node (ref "C31") (pin "1") (pinfunction "C1_1") (pintype "passive"))
      (node (ref "C32") (pin "2") (pinfunction "C2_2") (pintype "passive"))
      (node (ref "C7") (pin "2") (pinfunction "C2_2") (pintype "passive"))
      (node (ref "JP2") (pin "1") (pinfunction "A_1") (pintype "passive"))
      (node (ref "LC") (pin "1") (pinfunction "1_1") (pintype "passive"))
      (node (ref "Q2") (pin "P6") (pinfunction "VCC_P6") (pintype "power_in"))
      (node (ref "SJ_ISM") (pin "2") (pinfunction "2_2") (pintype "passive"))
      (node (ref "U12") (pin "6") (pinfunction "VDD_6") (pintype "power_in"))
      (node (ref "U12") (pin "8") (pinfunction "VDD_8") (pintype "power_in"))
    )
    (net (code "75") (name "unconnected-(Q2-N.C-PadP5)") (class "Default")
      (node (ref "Q2") (pin "P5") (pinfunction "N.C_P5") (pintype "no_connect"))
    )
    (net (code "76") (name "unconnected-(Q2-N.C.-PadP2)") (class "Default")
      (node (ref "Q2") (pin "P2") (pinfunction "N.C._P2") (pintype "no_connect"))
    )
    (net (code "77") (name "unconnected-(SJ5-Pad2)") (class "Default")
      (node (ref "SJ5") (pin "2") (pinfunction "2_2") (pintype "passive"))
    )
    (net (code "78") (name "unconnected-(U12-NC-Pad5)") (class "Default")
      (node (ref "U12") (pin "5") (pinfunction "NC_5") (pintype "no_connect"))
    )
    (net (code "79") (name "unconnected-(U12-XOUT-Pad16)") (class "Default")
      (node (ref "U12") (pin "16") (pinfunction "XOUT_16") (pintype "output"))
    )
  )
)
